# FL-Ver0_7.net
KiCad netlist of a schematic drawn in EAGLE
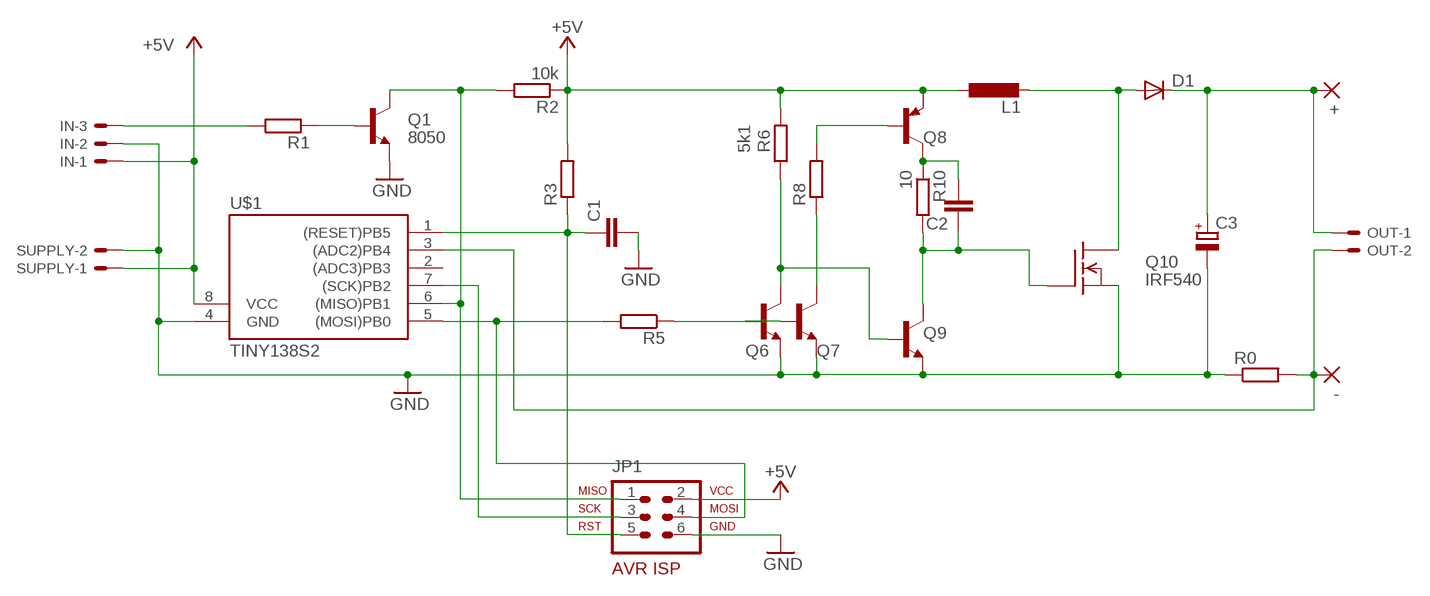
[diagram p0: schematic, sheet 1]

(export (version "E")
  (design (tool "Eeschema 10.0.6"))
  (components
    (comp (ref "+")
      (value "1,6/0,9")
      (footprint "eagle-import:1,6_0,9")
      (libsource (lib "eagle-import") (part "1,6/0,9"))
    )
    (comp (ref "-")
      (value "1,6/0,9")
      (footprint "eagle-import:1,6_0,9")
      (libsource (lib "eagle-import") (part "1,6/0,9"))
    )
    (comp (ref "C1")
      (value "C-EUC0805")
      (footprint "eagle-import:C0805")
      (libsource (lib "eagle-import") (part "C-EUC0805"))
    )
    (comp (ref "C2")
      (value "C-EUC0805")
      (footprint "eagle-import:C0805")
      (libsource (lib "eagle-import") (part "C-EUC0805"))
    )
    (comp (ref "C3")
      (value "CPOL-EU153CLV-0807")
      (footprint "eagle-import:153CLV-0807")
      (libsource (lib "eagle-import") (part "CPOL-EU153CLV-0807"))
    )
    (comp (ref "D1")
      (value "DIODE-SMB")
      (footprint "eagle-import:SMB")
      (libsource (lib "eagle-import") (part "DIODE-SMB"))
    )
    (comp (ref "IN")
      (value "22-23-2031")
      (footprint "eagle-import:22-23-2031")
      (libsource (lib "eagle-import") (part "22-23-2031"))
    )
    (comp (ref "JP1")
      (value "AVR-ISP-6VERT")
      (footprint "eagle-import:AVR-ISP-6")
      (libsource (lib "eagle-import") (part "AVR-ISP-6VERT"))
    )
    (comp (ref "L1")
      (value "DO3316P")
      (footprint "eagle-import:DO3316P")
      (libsource (lib "eagle-import") (part "DO3316P"))
    )
    (comp (ref "OUT")
      (value "22-23-2021")
      (footprint "eagle-import:22-23-2021")
      (libsource (lib "eagle-import") (part "22-23-2021"))
    )
    (comp (ref "Q1")
      (value "8050")
      (footprint "eagle-import:SOT23-BEC")
      (libsource (lib "eagle-import") (part "SS8050SMDSMD"))
    )
    (comp (ref "Q6")
      (value "SS8050SMDSMD")
      (footprint "eagle-import:SOT23-BEC")
      (libsource (lib "eagle-import") (part "SS8050SMDSMD"))
    )
    (comp (ref "Q7")
      (value "SS8050SMDSMD")
      (footprint "eagle-import:SOT23-BEC")
      (libsource (lib "eagle-import") (part "SS8050SMDSMD"))
    )
    (comp (ref "Q8")
      (value "SS8550SMDSMD")
      (footprint "eagle-import:SOT23-BEC")
      (libsource (lib "eagle-import") (part "SS8550SMDSMD"))
    )
    (comp (ref "Q9")
      (value "SS8050SMDSMD")
      (footprint "eagle-import:SOT23-BEC")
      (libsource (lib "eagle-import") (part "SS8050SMDSMD"))
    )
    (comp (ref "Q10")
      (value "IRF540")
      (footprint "eagle-import:TO220")
      (libsource (lib "eagle-import") (part "IRF540"))
    )
    (comp (ref "R0")
      (value "R-EU_0613/15")
      (footprint "eagle-import:P0613_15")
      (libsource (lib "eagle-import") (part "_resistor_R-EU_0613/15"))
    )
    (comp (ref "R1")
      (value "R-EU_M0805")
      (footprint "eagle-import:M0805")
      (libsource (lib "eagle-import") (part "R-EU_M0805"))
    )
    (comp (ref "R2")
      (value "10k")
      (footprint "eagle-import:M0805")
      (libsource (lib "eagle-import") (part "R-EU_M0805"))
    )
    (comp (ref "R3")
      (value "R-EU_M0805")
      (footprint "eagle-import:M0805")
      (libsource (lib "eagle-import") (part "R-EU_M0805"))
    )
    (comp (ref "R5")
      (value "R-EU_M0805")
      (footprint "eagle-import:M0805")
      (libsource (lib "eagle-import") (part "R-EU_M0805"))
    )
    (comp (ref "R6")
      (value "5k1")
      (footprint "eagle-import:M0805")
      (libsource (lib "eagle-import") (part "R-EU_M0805"))
    )
    (comp (ref "R8")
      (value "R-EU_M0805")
      (footprint "eagle-import:M0805")
      (libsource (lib "eagle-import") (part "R-EU_M0805"))
    )
    (comp (ref "R10")
      (value "10")
      (footprint "eagle-import:M0805")
      (libsource (lib "eagle-import") (part "R-EU_M0805"))
    )
    (comp (ref "SUPPLY")
      (value "22-23-2021")
      (footprint "eagle-import:22-23-2021")
      (libsource (lib "eagle-import") (part "22-23-2021"))
    )
    (comp (ref "U$1")
      (value "TINY138S2")
      (footprint "eagle-import:SO08")
      (libsource (lib "eagle-import") (part "TINY138S2"))
    )
  )
  (nets
    (net (code "1") (name "+5V") (class "Default")
      (node (ref "IN") (pin "1") (pinfunction "S_1") (pintype "passive"))
      (node (ref "JP1") (pin "2") (pinfunction "2_2") (pintype "passive"))
      (node (ref "L1") (pin "2") (pinfunction "2_2") (pintype "passive"))
      (node (ref "Q8") (pin "E") (pinfunction "E_E") (pintype "passive"))
      (node (ref "R2") (pin "1") (pinfunction "1_1") (pintype "passive"))
      (node (ref "R3") (pin "2") (pinfunction "2_2") (pintype "passive"))
      (node (ref "R6") (pin "2") (pinfunction "2_2") (pintype "passive"))
      (node (ref "SUPPLY") (pin "1") (pinfunction "S_1") (pintype "passive"))
      (node (ref "U$1") (pin "8") (pinfunction "VCC_8") (pintype "power_in"))
    )
    (net (code "2") (name "GND") (class "Default")
      (node (ref "C1") (pin "2") (pinfunction "2_2") (pintype "passive"))
      (node (ref "C3") (pin "-") (pinfunction "-_-") (pintype "passive"))
      (node (ref "IN") (pin "2") (pinfunction "S_2") (pintype "passive"))
      (node (ref "JP1") (pin "6") (pinfunction "6_6") (pintype "passive"))
      (node (ref "Q1") (pin "E") (pinfunction "E_E") (pintype "passive"))
      (node (ref "Q10") (pin "3") (pinfunction "S_3") (pintype "passive"))
      (node (ref "Q6") (pin "E") (pinfunction "E_E") (pintype "passive"))
      (node (ref "Q7") (pin "E") (pinfunction "E_E") (pintype "passive"))
      (node (ref "Q9") (pin "E") (pinfunction "E_E") (pintype "passive"))
      (node (ref "R0") (pin "1") (pinfunction "1_1") (pintype "passive"))
      (node (ref "SUPPLY") (pin "2") (pinfunction "S_2") (pintype "passive"))
      (node (ref "U$1") (pin "4") (pinfunction "GND_4") (pintype "power_in"))
    )
    (net (code "3") (name "Net-(+-P)") (class "Default")
      (node (ref "+") (pin "1") (pinfunction "P_1") (pintype "passive"))
      (node (ref "C3") (pin "+") (pinfunction "+_+") (pintype "passive"))
      (node (ref "D1") (pin "C") (pinfunction "C_C") (pintype "passive"))
      (node (ref "OUT") (pin "1") (pinfunction "S_1") (pintype "passive"))
    )
    (net (code "4") (name "Net-(--P)") (class "Default")
      (node (ref "-") (pin "1") (pinfunction "P_1") (pintype "passive"))
      (node (ref "OUT") (pin "2") (pinfunction "S_2") (pintype "passive"))
      (node (ref "R0") (pin "2") (pinfunction "2_2") (pintype "passive"))
      (node (ref "U$1") (pin "3") (pinfunction "(ADC2)PB4_3") (pintype "bidirectional"))
    )
    (net (code "5") (name "Net-(C2-Pad2)") (class "Default")
      (node (ref "C2") (pin "2") (pinfunction "2_2") (pintype "passive"))
      (node (ref "Q8") (pin "C") (pinfunction "C_C") (pintype "passive"))
      (node (ref "R10") (pin "1") (pinfunction "1_1") (pintype "passive"))
    )
    (net (code "6") (name "Net-(INC-S)") (class "Default")
      (node (ref "IN") (pin "3") (pinfunction "S_3") (pintype "passive"))
      (node (ref "R1") (pin "2") (pinfunction "2_2") (pintype "passive"))
    )
    (net (code "7") (name "Net-(Q1-PadB)") (class "Default")
      (node (ref "Q1") (pin "B") (pinfunction "B_B") (pintype "passive"))
      (node (ref "R1") (pin "1") (pinfunction "1_1") (pintype "passive"))
    )
    (net (code "8") (name "Net-(Q6-PadB)") (class "Default")
      (node (ref "Q6") (pin "B") (pinfunction "B_B") (pintype "passive"))
      (node (ref "Q7") (pin "B") (pinfunction "B_B") (pintype "passive"))
      (node (ref "R5") (pin "1") (pinfunction "1_1") (pintype "passive"))
    )
    (net (code "9") (name "Net-(Q6-PadC)") (class "Default")
      (node (ref "Q6") (pin "C") (pinfunction "C_C") (pintype "passive"))
      (node (ref "Q9") (pin "B") (pinfunction "B_B") (pintype "passive"))
      (node (ref "R6") (pin "1") (pinfunction "1_1") (pintype "passive"))
    )
    (net (code "10") (name "Net-(Q7-PadC)") (class "Default")
      (node (ref "Q7") (pin "C") (pinfunction "C_C") (pintype "passive"))
      (node (ref "R8") (pin "1") (pinfunction "1_1") (pintype "passive"))
    )
    (net (code "11") (name "Net-(Q8-PadB)") (class "Default")
      (node (ref "Q8") (pin "B") (pinfunction "B_B") (pintype "passive"))
      (node (ref "R8") (pin "2") (pinfunction "2_2") (pintype "passive"))
    )
    (net (code "12") (name "Net-(Q10-D)") (class "Default")
      (node (ref "D1") (pin "A") (pinfunction "A_A") (pintype "passive"))
      (node (ref "L1") (pin "1") (pinfunction "1_1") (pintype "passive"))
      (node (ref "Q10") (pin "2") (pinfunction "D_2") (pintype "passive"))
    )
    (net (code "13") (name "Net-(Q10-G)") (class "Default")
      (node (ref "C2") (pin "1") (pinfunction "1_1") (pintype "passive"))
      (node (ref "Q10") (pin "1") (pinfunction "G_1") (pintype "passive"))
      (node (ref "Q9") (pin "C") (pinfunction "C_C") (pintype "passive"))
      (node (ref "R10") (pin "2") (pinfunction "2_2") (pintype "passive"))
    )
    (net (code "14") (name "Net-(U$1-(MISO)PB1)") (class "Default")
      (node (ref "JP1") (pin "1") (pinfunction "1_1") (pintype "passive"))
      (node (ref "Q1") (pin "C") (pinfunction "C_C") (pintype "passive"))
      (node (ref "R2") (pin "2") (pinfunction "2_2") (pintype "passive"))
      (node (ref "U$1") (pin "6") (pinfunction "(MISO)PB1_6") (pintype "bidirectional"))
    )
    (net (code "15") (name "Net-(U$1-(MOSI)PB0)") (class "Default")
      (node (ref "JP1") (pin "4") (pinfunction "4_4") (pintype "passive"))
      (node (ref "R5") (pin "2") (pinfunction "2_2") (pintype "passive"))
      (node (ref "U$1") (pin "5") (pinfunction "(MOSI)PB0_5") (pintype "bidirectional"))
    )
    (net (code "16") (name "Net-(U$1-(RESET)PB5)") (class "Default")
      (node (ref "C1") (pin "1") (pinfunction "1_1") (pintype "passive"))
      (node (ref "JP1") (pin "5") (pinfunction "5_5") (pintype "passive"))
      (node (ref "R3") (pin "1") (pinfunction "1_1") (pintype "passive"))
      (node (ref "U$1") (pin "1") (pinfunction "(RESET)PB5_1") (pintype "bidirectional"))
    )
    (net (code "17") (name "Net-(U$1-(SCK)PB2)") (class "Default")
      (node (ref "JP1") (pin "3") (pinfunction "3_3") (pintype "passive"))
      (node (ref "U$1") (pin "7") (pinfunction "(SCK)PB2_7") (pintype "bidirectional"))
    )
    (net (code "18") (name "unconnected-(U$1-(ADC3)PB3-Pad2)") (class "Default")
      (node (ref "U$1") (pin "2") (pinfunction "(ADC3)PB3_2") (pintype "bidirectional"))
    )
  )
)
